# troostite_1_0v.net
KiCad netlist of a schematic drawn in EAGLE
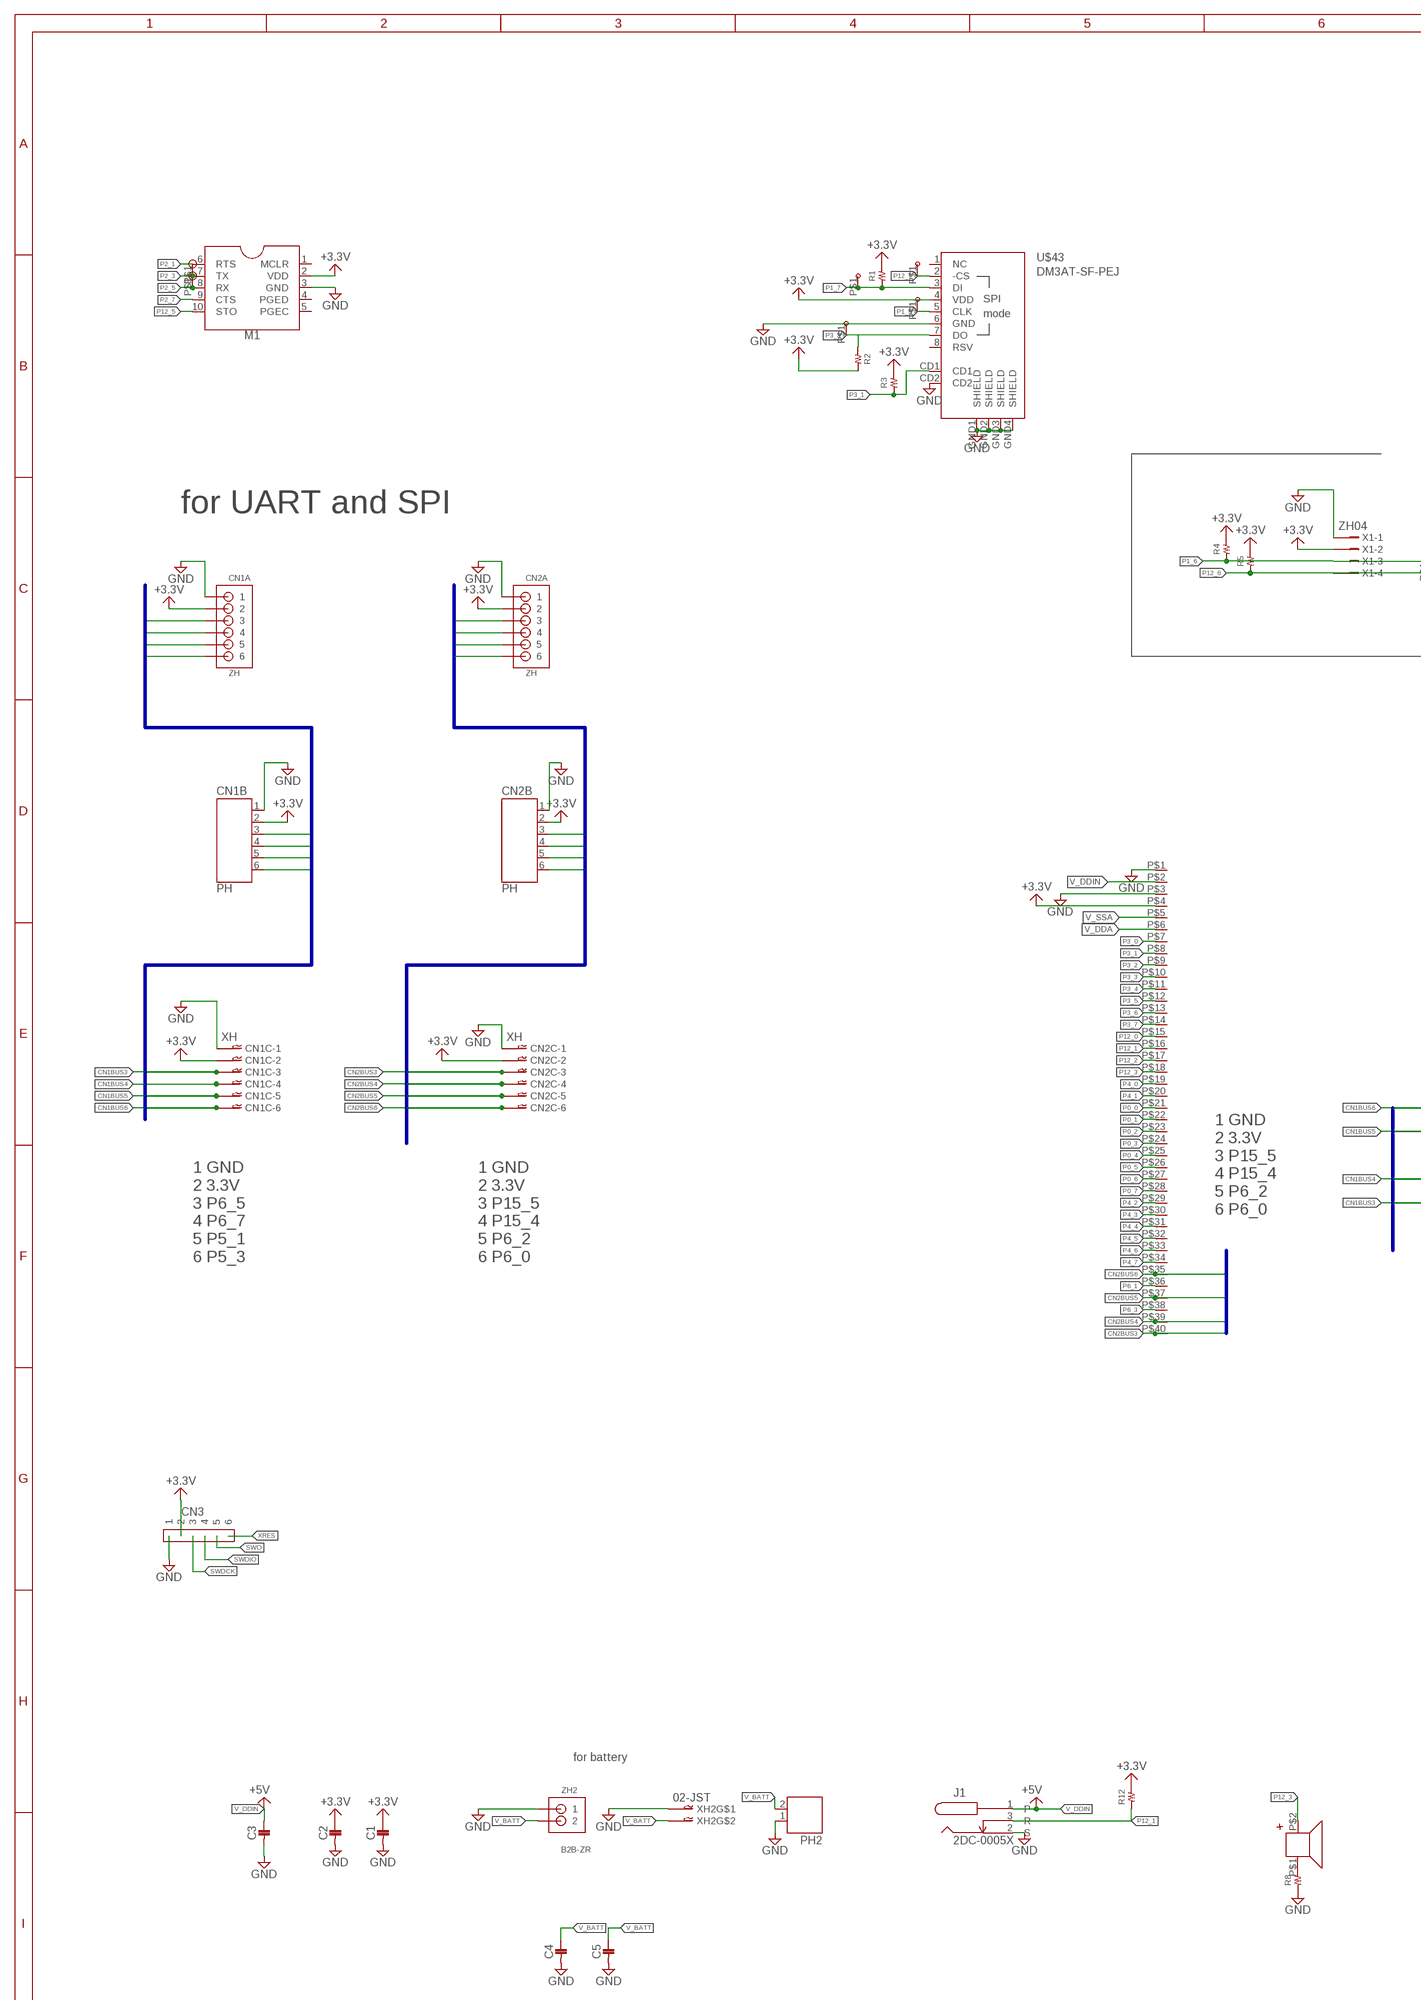
[diagram p0: schematic, sheet 1, part 1 of 2]
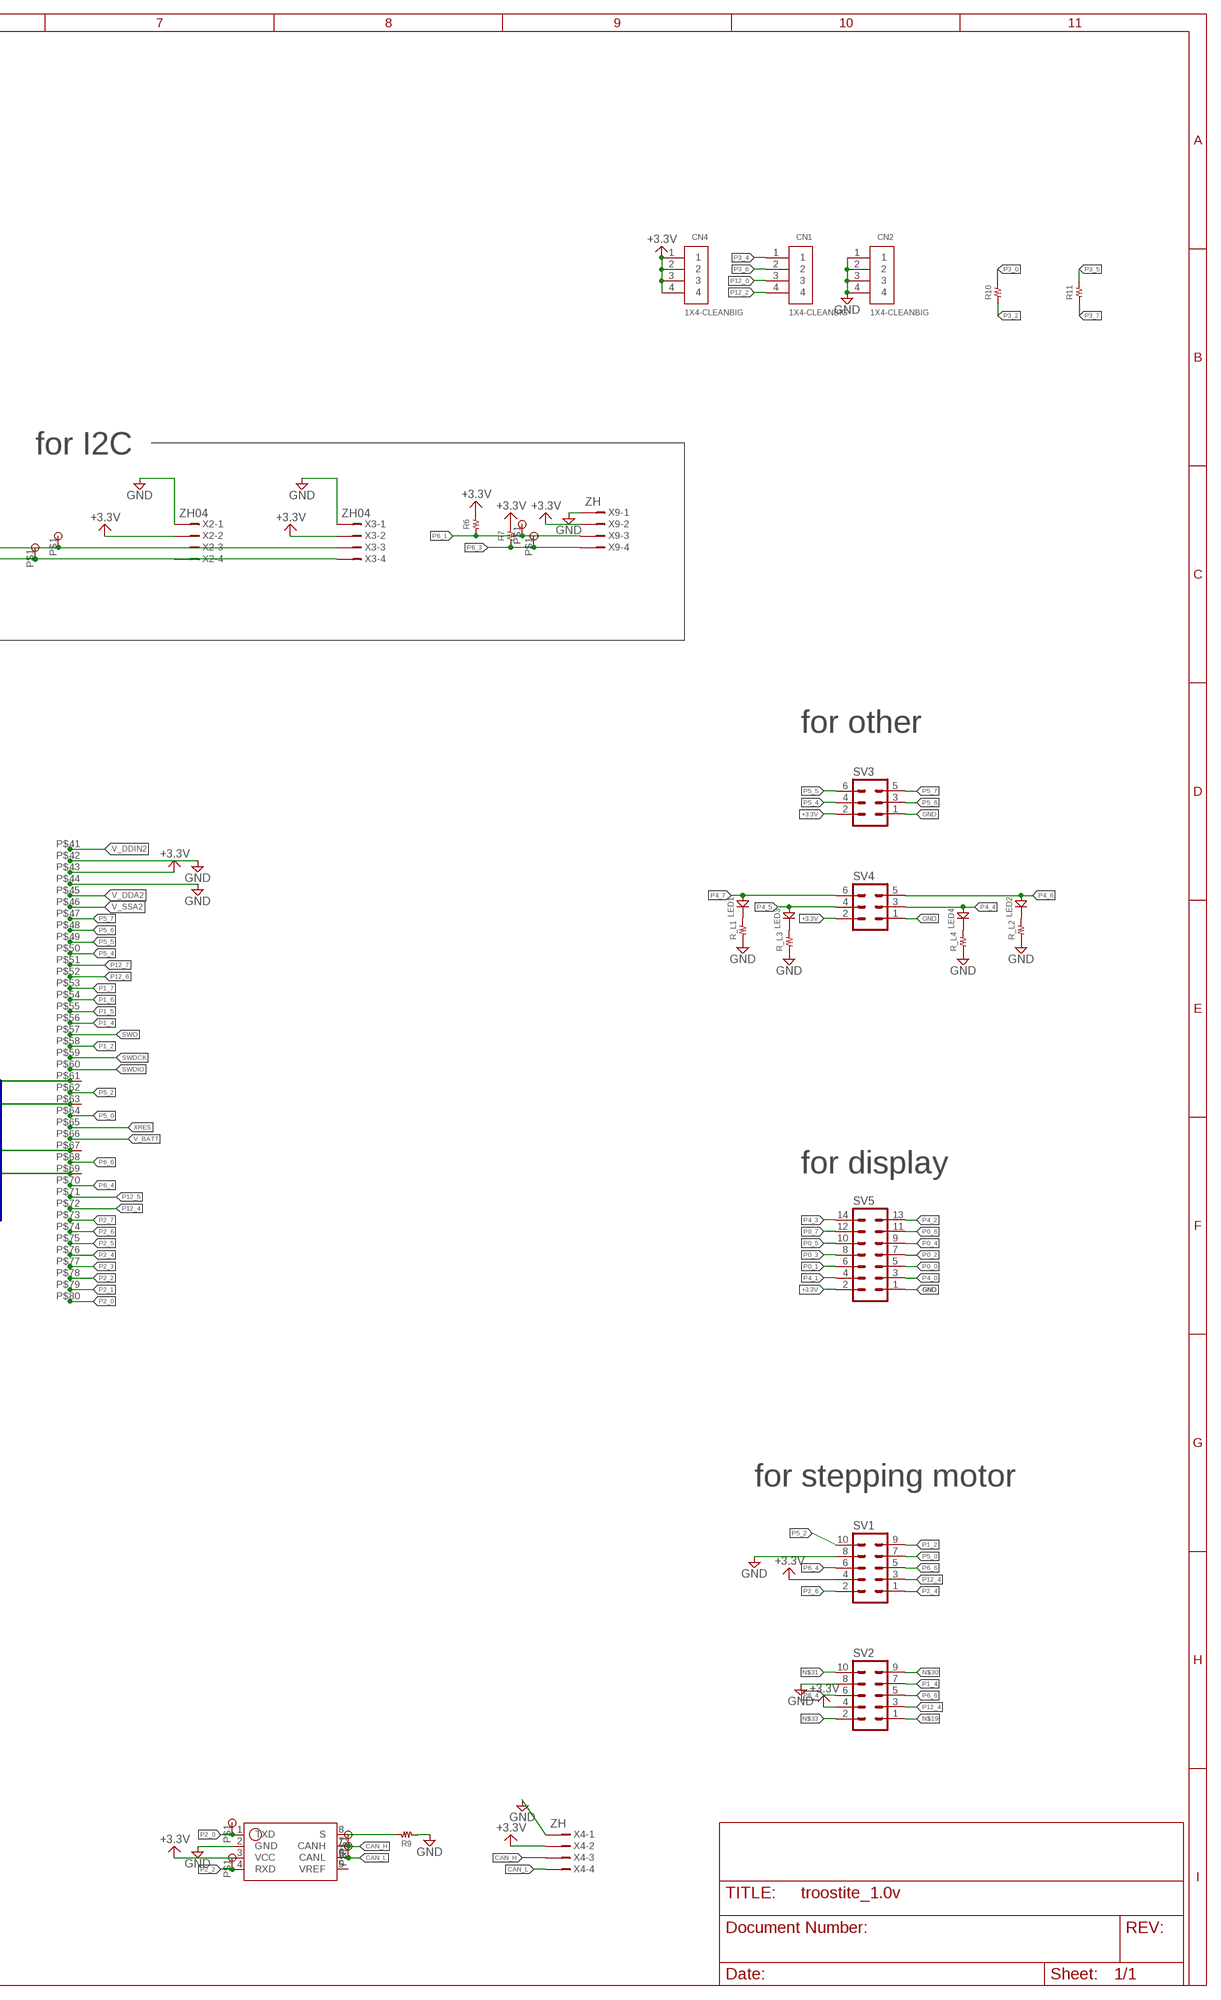
[diagram p1: schematic, sheet 1, part 2 of 2]

(export (version "E")
  (design (tool "Eeschema 10.0.6"))
  (components
    (comp (ref "C1")
      (value "1608")
      (footprint "eagle-import:1608")
      (libsource (lib "eagle-import") (part "1608"))
    )
    (comp (ref "C2")
      (value "1608")
      (footprint "eagle-import:1608")
      (libsource (lib "eagle-import") (part "1608"))
    )
    (comp (ref "C3")
      (value "1608")
      (footprint "eagle-import:1608")
      (libsource (lib "eagle-import") (part "1608"))
    )
    (comp (ref "C4")
      (value "1608")
      (footprint "eagle-import:1608")
      (libsource (lib "eagle-import") (part "1608"))
    )
    (comp (ref "C5")
      (value "3225")
      (footprint "eagle-import:3225")
      (libsource (lib "eagle-import") (part "3225"))
    )
    (comp (ref "CN1")
      (value "1X4-CLEANBIG")
      (footprint "eagle-import:1X04-CLEANBIG")
      (libsource (lib "eagle-import") (part "1X4-CLEANBIG"))
    )
    (comp (ref "CN1A")
      (value "ZH")
      (footprint "eagle-import:B6B-ZR")
      (libsource (lib "eagle-import") (part "B6B-ZR"))
    )
    (comp (ref "CN1B")
      (value "PH")
      (footprint "eagle-import:JST-PH6")
      (libsource (lib "eagle-import") (part "JST-PH6"))
    )
    (comp (ref "CN1C")
      (value "XH")
      (footprint "eagle-import:B6B-XH")
      (libsource (lib "eagle-import") (part "06-JST-B6B-XH-A"))
    )
    (comp (ref "CN2")
      (value "1X4-CLEANBIG")
      (footprint "eagle-import:1X04-CLEANBIG")
      (libsource (lib "eagle-import") (part "1X4-CLEANBIG"))
    )
    (comp (ref "CN2A")
      (value "ZH")
      (footprint "eagle-import:B6B-ZR")
      (libsource (lib "eagle-import") (part "B6B-ZR"))
    )
    (comp (ref "CN2B")
      (value "PH")
      (footprint "eagle-import:JST-PH6")
      (libsource (lib "eagle-import") (part "JST-PH6"))
    )
    (comp (ref "CN2C")
      (value "XH")
      (footprint "eagle-import:B6B-XH")
      (libsource (lib "eagle-import") (part "06-JST-B6B-XH-A"))
    )
    (comp (ref "CN3")
      (value "PIN_HEADER_6")
      (footprint "eagle-import:PIN_HEADER_6")
      (libsource (lib "eagle-import") (part "PIN_HEADER_6"))
    )
    (comp (ref "CN4")
      (value "1X4-CLEANBIG")
      (footprint "eagle-import:1X04-CLEANBIG")
      (libsource (lib "eagle-import") (part "1X4-CLEANBIG"))
    )
    (comp (ref "IC1")
      (value "SN65HVD1050")
      (footprint "eagle-import:SOIC8")
      (libsource (lib "eagle-import") (part "SN65HVD1050"))
    )
    (comp (ref "J1")
      (value "2DC-0005X")
      (footprint "eagle-import:2DC-0005D")
      (libsource (lib "eagle-import") (part "2DC-0005X"))
    )
    (comp (ref "LED1")
      (value "CHIPLED")
      (footprint "eagle-import:1608")
      (libsource (lib "eagle-import") (part "CHIPLED"))
    )
    (comp (ref "LED2")
      (value "CHIPLED")
      (footprint "eagle-import:1608")
      (libsource (lib "eagle-import") (part "CHIPLED"))
    )
    (comp (ref "LED3")
      (value "CHIPLED")
      (footprint "eagle-import:1608")
      (libsource (lib "eagle-import") (part "CHIPLED"))
    )
    (comp (ref "LED4")
      (value "CHIPLED")
      (footprint "eagle-import:1608")
      (libsource (lib "eagle-import") (part "CHIPLED"))
    )
    (comp (ref "M1")
      (value "SBDBT")
      (footprint "eagle-import:DIL10")
      (libsource (lib "eagle-import") (part "SBDBT"))
    )
    (comp (ref "PH2")
      (value "JST-PH2")
      (footprint "eagle-import:JST-PH2")
      (libsource (lib "eagle-import") (part "JST-PH2"))
    )
    (comp (ref "R1")
      (value "RESISTOR__SMD")
      (footprint "eagle-import:1608")
      (libsource (lib "eagle-import") (part "RESISTOR__SMD"))
    )
    (comp (ref "R2")
      (value "RESISTOR__SMD")
      (footprint "eagle-import:1608")
      (libsource (lib "eagle-import") (part "RESISTOR__SMD"))
    )
    (comp (ref "R3")
      (value "RESISTOR__SMD")
      (footprint "eagle-import:1608")
      (libsource (lib "eagle-import") (part "RESISTOR__SMD"))
    )
    (comp (ref "R4")
      (value "RESISTOR__SMD")
      (footprint "eagle-import:1608")
      (libsource (lib "eagle-import") (part "RESISTOR__SMD"))
    )
    (comp (ref "R5")
      (value "RESISTOR__SMD")
      (footprint "eagle-import:1608")
      (libsource (lib "eagle-import") (part "RESISTOR__SMD"))
    )
    (comp (ref "R6")
      (value "RESISTOR__SMD")
      (footprint "eagle-import:1608")
      (libsource (lib "eagle-import") (part "RESISTOR__SMD"))
    )
    (comp (ref "R7")
      (value "RESISTOR__SMD")
      (footprint "eagle-import:1608")
      (libsource (lib "eagle-import") (part "RESISTOR__SMD"))
    )
    (comp (ref "R8")
      (value "RESISTOR__SMD")
      (footprint "eagle-import:1608")
      (libsource (lib "eagle-import") (part "RESISTOR__SMD"))
    )
    (comp (ref "R9")
      (value "RESISTOR__SMD")
      (footprint "eagle-import:1608")
      (libsource (lib "eagle-import") (part "RESISTOR__SMD"))
    )
    (comp (ref "R10")
      (value "RESISTOR__SMD")
      (footprint "eagle-import:1608")
      (libsource (lib "eagle-import") (part "RESISTOR__SMD"))
    )
    (comp (ref "R11")
      (value "RESISTOR__SMD")
      (footprint "eagle-import:1608")
      (libsource (lib "eagle-import") (part "RESISTOR__SMD"))
    )
    (comp (ref "R12")
      (value "RESISTOR__SMD")
      (footprint "eagle-import:1608")
      (libsource (lib "eagle-import") (part "RESISTOR__SMD"))
    )
    (comp (ref "R_L1")
      (value "RESISTOR__SMD")
      (footprint "eagle-import:1608")
      (libsource (lib "eagle-import") (part "RESISTOR__SMD"))
    )
    (comp (ref "R_L2")
      (value "RESISTOR__SMD")
      (footprint "eagle-import:1608")
      (libsource (lib "eagle-import") (part "RESISTOR__SMD"))
    )
    (comp (ref "R_L3")
      (value "RESISTOR__SMD")
      (footprint "eagle-import:1608")
      (libsource (lib "eagle-import") (part "RESISTOR__SMD"))
    )
    (comp (ref "R_L4")
      (value "RESISTOR__SMD")
      (footprint "eagle-import:1608")
      (libsource (lib "eagle-import") (part "RESISTOR__SMD"))
    )
    (comp (ref "SV1")
      (value "ML10")
      (footprint "eagle-import:ML10")
      (libsource (lib "eagle-import") (part "ML10"))
    )
    (comp (ref "SV2")
      (value "ML10")
      (footprint "eagle-import:ML10")
      (libsource (lib "eagle-import") (part "ML10"))
    )
    (comp (ref "SV3")
      (value "ML6")
      (footprint "eagle-import:ML6")
      (libsource (lib "eagle-import") (part "ML6"))
    )
    (comp (ref "SV4")
      (value "ML6")
      (footprint "eagle-import:ML6")
      (libsource (lib "eagle-import") (part "ML6"))
    )
    (comp (ref "SV5")
      (value "ML14")
      (footprint "eagle-import:ML14")
      (libsource (lib "eagle-import") (part "ML14"))
    )
    (comp (ref "U$2")
      (value "PSOC_5LP")
      (footprint "eagle-import:PSOC_5LP")
      (libsource (lib "eagle-import") (part "PSOC_5LP"))
    )
    (comp (ref "U$41")
      (value "PKLCS1212E4001")
      (footprint "eagle-import:PKLCS1212E4001")
      (libsource (lib "eagle-import") (part "PKLCS1212E4001"))
    )
    (comp (ref "U$43")
      (value "DM3AT-SF-PEJ")
      (footprint "eagle-import:DM3AT-SF-PEJ")
      (libsource (lib "eagle-import") (part "DM3AT-SF-PEJ"))
    )
    (comp (ref "U$72")
      (value "CHECK_0.8MM")
      (footprint "eagle-import:CHECK_0.8MM")
      (libsource (lib "eagle-import") (part "CHECK_0.8MM"))
    )
    (comp (ref "U$73")
      (value "CHECK_0.8MM")
      (footprint "eagle-import:CHECK_0.8MM")
      (libsource (lib "eagle-import") (part "CHECK_0.8MM"))
    )
    (comp (ref "U$74")
      (value "CHECK_0.8MM")
      (footprint "eagle-import:CHECK_0.8MM")
      (libsource (lib "eagle-import") (part "CHECK_0.8MM"))
    )
    (comp (ref "U$75")
      (value "CHECK_0.8MM")
      (footprint "eagle-import:CHECK_0.8MM")
      (libsource (lib "eagle-import") (part "CHECK_0.8MM"))
    )
    (comp (ref "U$76")
      (value "CHECK_0.8MM")
      (footprint "eagle-import:CHECK_0.8MM")
      (libsource (lib "eagle-import") (part "CHECK_0.8MM"))
    )
    (comp (ref "U$77")
      (value "CHECK_0.8MM")
      (footprint "eagle-import:CHECK_0.8MM")
      (libsource (lib "eagle-import") (part "CHECK_0.8MM"))
    )
    (comp (ref "U$78")
      (value "CHECK_0.8MM")
      (footprint "eagle-import:CHECK_0.8MM")
      (libsource (lib "eagle-import") (part "CHECK_0.8MM"))
    )
    (comp (ref "U$79")
      (value "CHECK_0.8MM")
      (footprint "eagle-import:CHECK_0.8MM")
      (libsource (lib "eagle-import") (part "CHECK_0.8MM"))
    )
    (comp (ref "U$82")
      (value "CHECK_0.8MM")
      (footprint "eagle-import:CHECK_0.8MM")
      (libsource (lib "eagle-import") (part "CHECK_0.8MM"))
    )
    (comp (ref "U$83")
      (value "CHECK_0.8MM")
      (footprint "eagle-import:CHECK_0.8MM")
      (libsource (lib "eagle-import") (part "CHECK_0.8MM"))
    )
    (comp (ref "U$85")
      (value "CHECK_21.3")
      (footprint "eagle-import:CHECK_2_1.3")
      (libsource (lib "eagle-import") (part "CHECK_21.3"))
    )
    (comp (ref "U$86")
      (value "CHECK_21.3")
      (footprint "eagle-import:CHECK_2_1.3")
      (libsource (lib "eagle-import") (part "CHECK_21.3"))
    )
    (comp (ref "U$87")
      (value "CHECK_21.3")
      (footprint "eagle-import:CHECK_2_1.3")
      (libsource (lib "eagle-import") (part "CHECK_21.3"))
    )
    (comp (ref "U$88")
      (value "CHECK_21.3")
      (footprint "eagle-import:CHECK_2_1.3")
      (libsource (lib "eagle-import") (part "CHECK_21.3"))
    )
    (comp (ref "X1")
      (value "ZH04")
      (footprint "eagle-import:B4B-ZR")
      (fields (field (name "MF") "FARNELL") (field (name "MPN") "B4B-ZR(LF)(SN)"))
      (libsource (lib "eagle-import") (part "?4B-ZRB"))
    )
    (comp (ref "X2")
      (value "ZH04")
      (footprint "eagle-import:B4B-ZR")
      (fields (field (name "MF") "FARNELL") (field (name "MPN") "B4B-ZR(LF)(SN)"))
      (libsource (lib "eagle-import") (part "?4B-ZRB"))
    )
    (comp (ref "X3")
      (value "ZH04")
      (footprint "eagle-import:B4B-ZR")
      (fields (field (name "MF") "FARNELL") (field (name "MPN") "B4B-ZR(LF)(SN)"))
      (libsource (lib "eagle-import") (part "?4B-ZRB"))
    )
    (comp (ref "X4")
      (value "ZH")
      (footprint "eagle-import:B4B-ZR")
      (fields (field (name "MF") "FARNELL") (field (name "MPN") "B4B-ZR(LF)(SN)"))
      (libsource (lib "eagle-import") (part "?4B-ZRB"))
    )
    (comp (ref "X9")
      (value "ZH")
      (footprint "eagle-import:B4B-ZR")
      (fields (field (name "MF") "FARNELL") (field (name "MPN") "B4B-ZR(LF)(SN)"))
      (libsource (lib "eagle-import") (part "?4B-ZRB"))
    )
    (comp (ref "XH2")
      (value "02-JST")
      (footprint "eagle-import:B2B-XH")
      (libsource (lib "eagle-import") (part "02-JST"))
    )
    (comp (ref "ZH2")
      (value "B2B-ZR")
      (footprint "eagle-import:B2B-ZR")
      (libsource (lib "eagle-import") (part "B2B-ZR"))
    )
  )
  (nets
    (net (code "1") (name "+3.3V") (class "Default")
      (node (ref "C1") (pin "P$1") (pinfunction "1_P$1") (pintype "passive"))
      (node (ref "C2") (pin "P$1") (pinfunction "1_P$1") (pintype "passive"))
      (node (ref "CN1A") (pin "2") (pinfunction "2_2") (pintype "bidirectional"))
      (node (ref "CN1B") (pin "2") (pinfunction "2_2") (pintype "passive"))
      (node (ref "CN1C") (pin "P$2") (pinfunction "1_P$2") (pintype "passive"))
      (node (ref "CN2A") (pin "2") (pinfunction "2_2") (pintype "bidirectional"))
      (node (ref "CN2B") (pin "2") (pinfunction "2_2") (pintype "passive"))
      (node (ref "CN2C") (pin "P$2") (pinfunction "1_P$2") (pintype "passive"))
      (node (ref "CN3") (pin "2") (pinfunction "2_2") (pintype "bidirectional"))
      (node (ref "CN4") (pin "1") (pinfunction "1_1") (pintype "bidirectional"))
      (node (ref "CN4") (pin "2") (pinfunction "2_2") (pintype "bidirectional"))
      (node (ref "CN4") (pin "3") (pinfunction "3_3") (pintype "bidirectional"))
      (node (ref "CN4") (pin "4") (pinfunction "4_4") (pintype "bidirectional"))
      (node (ref "IC1") (pin "3") (pinfunction "VCC_3") (pintype "bidirectional"))
      (node (ref "M1") (pin "2") (pinfunction "VDD_2") (pintype "passive"))
      (node (ref "R1") (pin "2") (pinfunction "P$2_2") (pintype "passive"))
      (node (ref "R12") (pin "2") (pinfunction "P$2_2") (pintype "passive"))
      (node (ref "R2") (pin "2") (pinfunction "P$2_2") (pintype "passive"))
      (node (ref "R3") (pin "2") (pinfunction "P$2_2") (pintype "passive"))
      (node (ref "R4") (pin "2") (pinfunction "P$2_2") (pintype "passive"))
      (node (ref "R5") (pin "2") (pinfunction "P$2_2") (pintype "passive"))
      (node (ref "R6") (pin "2") (pinfunction "P$2_2") (pintype "passive"))
      (node (ref "R7") (pin "2") (pinfunction "P$2_2") (pintype "passive"))
      (node (ref "SV1") (pin "4") (pinfunction "4_4") (pintype "passive"))
      (node (ref "SV2") (pin "4") (pinfunction "4_4") (pintype "passive"))
      (node (ref "SV3") (pin "2") (pinfunction "2_2") (pintype "passive"))
      (node (ref "SV4") (pin "2") (pinfunction "2_2") (pintype "passive"))
      (node (ref "SV5") (pin "2") (pinfunction "2_2") (pintype "passive"))
      (node (ref "U$2") (pin "P$4") (pinfunction "P$4_P$4") (pintype "bidirectional"))
      (node (ref "U$2") (pin "P$43") (pinfunction "P$43_P$43") (pintype "bidirectional"))
      (node (ref "U$43") (pin "4") (pinfunction "VDD_4") (pintype "bidirectional"))
      (node (ref "X1") (pin "2") (pinfunction "1_2") (pintype "passive"))
      (node (ref "X2") (pin "2") (pinfunction "1_2") (pintype "passive"))
      (node (ref "X3") (pin "2") (pinfunction "1_2") (pintype "passive"))
      (node (ref "X4") (pin "2") (pinfunction "1_2") (pintype "passive"))
      (node (ref "X9") (pin "2") (pinfunction "1_2") (pintype "passive"))
    )
    (net (code "4") (name "CAN_H") (class "Default")
      (node (ref "IC1") (pin "7") (pinfunction "CANH_7") (pintype "bidirectional"))
      (node (ref "U$72") (pin "P$1") (pinfunction "P$1_P$1") (pintype "bidirectional"))
      (node (ref "X4") (pin "3") (pinfunction "1_3") (pintype "passive"))
    )
    (net (code "5") (name "CAN_L") (class "Default")
      (node (ref "IC1") (pin "6") (pinfunction "CANL_6") (pintype "bidirectional"))
      (node (ref "U$73") (pin "P$1") (pinfunction "P$1_P$1") (pintype "bidirectional"))
      (node (ref "X4") (pin "4") (pinfunction "1_4") (pintype "passive"))
    )
    (net (code "6") (name "CN1BUS3") (class "Default")
      (node (ref "CN1A") (pin "3") (pinfunction "3_3") (pintype "bidirectional"))
      (node (ref "CN1B") (pin "3") (pinfunction "3_3") (pintype "passive"))
      (node (ref "CN1C") (pin "P$3") (pinfunction "1_P$3") (pintype "passive"))
      (node (ref "U$2") (pin "P$69") (pinfunction "P$69_P$69") (pintype "bidirectional"))
    )
    (net (code "7") (name "CN1BUS4") (class "Default")
      (node (ref "CN1A") (pin "4") (pinfunction "4_4") (pintype "bidirectional"))
      (node (ref "CN1B") (pin "4") (pinfunction "4_4") (pintype "passive"))
      (node (ref "CN1C") (pin "P$4") (pinfunction "1_P$4") (pintype "passive"))
      (node (ref "U$2") (pin "P$67") (pinfunction "P$67_P$67") (pintype "bidirectional"))
    )
    (net (code "8") (name "CN1BUS5") (class "Default")
      (node (ref "CN1A") (pin "5") (pinfunction "5_5") (pintype "bidirectional"))
      (node (ref "CN1B") (pin "5") (pinfunction "5_5") (pintype "passive"))
      (node (ref "CN1C") (pin "P$5") (pinfunction "1_P$5") (pintype "passive"))
      (node (ref "U$2") (pin "P$63") (pinfunction "P$63_P$63") (pintype "bidirectional"))
    )
    (net (code "9") (name "CN1BUS6") (class "Default")
      (node (ref "CN1A") (pin "6") (pinfunction "6_6") (pintype "bidirectional"))
      (node (ref "CN1B") (pin "6") (pinfunction "6_6") (pintype "passive"))
      (node (ref "CN1C") (pin "P$6") (pinfunction "1_P$6") (pintype "passive"))
      (node (ref "U$2") (pin "P$61") (pinfunction "P$61_P$61") (pintype "bidirectional"))
    )
    (net (code "10") (name "CN2BUS3") (class "Default")
      (node (ref "CN2A") (pin "3") (pinfunction "3_3") (pintype "bidirectional"))
      (node (ref "CN2B") (pin "3") (pinfunction "3_3") (pintype "passive"))
      (node (ref "CN2C") (pin "P$3") (pinfunction "1_P$3") (pintype "passive"))
      (node (ref "U$2") (pin "P$40") (pinfunction "P$40_P$40") (pintype "bidirectional"))
    )
    (net (code "11") (name "CN2BUS4") (class "Default")
      (node (ref "CN2A") (pin "4") (pinfunction "4_4") (pintype "bidirectional"))
      (node (ref "CN2B") (pin "4") (pinfunction "4_4") (pintype "passive"))
      (node (ref "CN2C") (pin "P$4") (pinfunction "1_P$4") (pintype "passive"))
      (node (ref "U$2") (pin "P$39") (pinfunction "P$39_P$39") (pintype "bidirectional"))
    )
    (net (code "12") (name "CN2BUS5") (class "Default")
      (node (ref "CN2A") (pin "5") (pinfunction "5_5") (pintype "bidirectional"))
      (node (ref "CN2B") (pin "5") (pinfunction "5_5") (pintype "passive"))
      (node (ref "CN2C") (pin "P$5") (pinfunction "1_P$5") (pintype "passive"))
      (node (ref "U$2") (pin "P$37") (pinfunction "P$37_P$37") (pintype "bidirectional"))
    )
    (net (code "13") (name "CN2BUS6") (class "Default")
      (node (ref "CN2A") (pin "6") (pinfunction "6_6") (pintype "bidirectional"))
      (node (ref "CN2B") (pin "6") (pinfunction "6_6") (pintype "passive"))
      (node (ref "CN2C") (pin "P$6") (pinfunction "1_P$6") (pintype "passive"))
      (node (ref "U$2") (pin "P$35") (pinfunction "P$35_P$35") (pintype "bidirectional"))
    )
    (net (code "14") (name "GND") (class "Default")
      (node (ref "C1") (pin "P$2") (pinfunction "2_P$2") (pintype "passive"))
      (node (ref "C2") (pin "P$2") (pinfunction "2_P$2") (pintype "passive"))
      (node (ref "C3") (pin "P$2") (pinfunction "2_P$2") (pintype "passive"))
      (node (ref "C4") (pin "P$2") (pinfunction "2_P$2") (pintype "passive"))
      (node (ref "C5") (pin "P$2") (pinfunction "2_P$2") (pintype "passive"))
      (node (ref "CN1A") (pin "1") (pinfunction "1_1") (pintype "bidirectional"))
      (node (ref "CN1B") (pin "1") (pinfunction "1_1") (pintype "passive"))
      (node (ref "CN1C") (pin "P$1") (pinfunction "1_P$1") (pintype "passive"))
      (node (ref "CN2") (pin "1") (pinfunction "1_1") (pintype "bidirectional"))
      (node (ref "CN2") (pin "2") (pinfunction "2_2") (pintype "bidirectional"))
      (node (ref "CN2") (pin "3") (pinfunction "3_3") (pintype "bidirectional"))
      (node (ref "CN2") (pin "4") (pinfunction "4_4") (pintype "bidirectional"))
      (node (ref "CN2A") (pin "1") (pinfunction "1_1") (pintype "bidirectional"))
      (node (ref "CN2B") (pin "1") (pinfunction "1_1") (pintype "passive"))
      (node (ref "CN2C") (pin "P$1") (pinfunction "1_P$1") (pintype "passive"))
      (node (ref "CN3") (pin "1") (pinfunction "1_1") (pintype "bidirectional"))
      (node (ref "IC1") (pin "2") (pinfunction "GND_2") (pintype "bidirectional"))
      (node (ref "J1") (pin "2") (pinfunction "S_2") (pintype "power_in"))
      (node (ref "M1") (pin "3") (pinfunction "GND_3") (pintype "passive"))
      (node (ref "PH2") (pin "1") (pinfunction "1_1") (pintype "passive"))
      (node (ref "R8") (pin "1") (pinfunction "P$1_1") (pintype "passive"))
      (node (ref "R9") (pin "1") (pinfunction "P$1_1") (pintype "passive"))
      (node (ref "R_L1") (pin "1") (pinfunction "P$1_1") (pintype "passive"))
      (node (ref "R_L2") (pin "1") (pinfunction "P$1_1") (pintype "passive"))
      (node (ref "R_L3") (pin "1") (pinfunction "P$1_1") (pintype "passive"))
      (node (ref "R_L4") (pin "1") (pinfunction "P$1_1") (pintype "passive"))
      (node (ref "SV1") (pin "8") (pinfunction "8_8") (pintype "passive"))
      (node (ref "SV2") (pin "8") (pinfunction "8_8") (pintype "passive"))
      (node (ref "SV3") (pin "1") (pinfunction "1_1") (pintype "passive"))
      (node (ref "SV4") (pin "1") (pinfunction "1_1") (pintype "passive"))
      (node (ref "SV5") (pin "1") (pinfunction "1_1") (pintype "passive"))
      (node (ref "U$2") (pin "P$1") (pinfunction "P$1_P$1") (pintype "bidirectional"))
      (node (ref "U$2") (pin "P$3") (pinfunction "P$3_P$3") (pintype "bidirectional"))
      (node (ref "U$2") (pin "P$42") (pinfunction "P$42_P$42") (pintype "bidirectional"))
      (node (ref "U$2") (pin "P$44") (pinfunction "P$44_P$44") (pintype "bidirectional"))
      (node (ref "U$43") (pin "6") (pinfunction "GND_6") (pintype "bidirectional"))
      (node (ref "U$43") (pin "CD2") (pinfunction "CD2_CD2") (pintype "bidirectional"))
      (node (ref "U$43") (pin "GND1") (pinfunction "SHIELD_GND1") (pintype "bidirectional"))
      (node (ref "U$43") (pin "GND2") (pinfunction "SHIELD_GND2") (pintype "bidirectional"))
      (node (ref "U$43") (pin "GND3") (pinfunction "SHIELD_GND3") (pintype "bidirectional"))
      (node (ref "U$43") (pin "GND4") (pinfunction "SHIELD_GND4") (pintype "bidirectional"))
      (node (ref "X1") (pin "1") (pinfunction "1_1") (pintype "passive"))
      (node (ref "X2") (pin "1") (pinfunction "1_1") (pintype "passive"))
      (node (ref "X3") (pin "1") (pinfunction "1_1") (pintype "passive"))
      (node (ref "X4") (pin "1") (pinfunction "1_1") (pintype "passive"))
      (node (ref "X9") (pin "1") (pinfunction "1_1") (pintype "passive"))
      (node (ref "XH2") (pin "P$1") (pinfunction "1_P$1") (pintype "passive"))
      (node (ref "ZH2") (pin "1") (pinfunction "1_1") (pintype "bidirectional"))
    )
    (net (code "15") (name "N$19") (class "Default")
      (node (ref "SV2") (pin "1") (pinfunction "1_1") (pintype "passive"))
    )
    (net (code "16") (name "N$30") (class "Default")
      (node (ref "SV2") (pin "9") (pinfunction "9_9") (pintype "passive"))
    )
    (net (code "17") (name "N$31") (class "Default")
      (node (ref "SV2") (pin "10") (pinfunction "10_10") (pintype "passive"))
    )
    (net (code "18") (name "N$33") (class "Default")
      (node (ref "SV2") (pin "2") (pinfunction "2_2") (pintype "passive"))
    )
    (net (code "19") (name "Net-(IC1-S)") (class "Default")
      (node (ref "IC1") (pin "8") (pinfunction "S_8") (pintype "bidirectional"))
      (node (ref "R9") (pin "2") (pinfunction "P$2_2") (pintype "passive"))
    )
    (net (code "20") (name "Net-(LED1-K)") (class "Default")
      (node (ref "LED1") (pin "2") (pinfunction "K_2") (pintype "bidirectional"))
      (node (ref "R_L1") (pin "2") (pinfunction "P$2_2") (pintype "passive"))
    )
    (net (code "21") (name "Net-(LED2-K)") (class "Default")
      (node (ref "LED2") (pin "2") (pinfunction "K_2") (pintype "bidirectional"))
      (node (ref "R_L2") (pin "2") (pinfunction "P$2_2") (pintype "passive"))
    )
    (net (code "22") (name "Net-(LED3-K)") (class "Default")
      (node (ref "LED3") (pin "2") (pinfunction "K_2") (pintype "bidirectional"))
      (node (ref "R_L3") (pin "2") (pinfunction "P$2_2") (pintype "passive"))
    )
    (net (code "23") (name "Net-(LED4-K)") (class "Default")
      (node (ref "LED4") (pin "2") (pinfunction "K_2") (pintype "bidirectional"))
      (node (ref "R_L4") (pin "2") (pinfunction "P$2_2") (pintype "passive"))
    )
    (net (code "24") (name "Net-(R8-P$2)") (class "Default")
      (node (ref "R8") (pin "2") (pinfunction "P$2_2") (pintype "passive"))
      (node (ref "U$41") (pin "P$1") (pinfunction "MINUS_P$1") (pintype "bidirectional"))
    )
    (net (code "25") (name "P0_0") (class "Default")
      (node (ref "SV5") (pin "5") (pinfunction "5_5") (pintype "passive"))
      (node (ref "U$2") (pin "P$21") (pinfunction "P$21_P$21") (pintype "bidirectional"))
    )
    (net (code "26") (name "P0_1") (class "Default")
      (node (ref "SV5") (pin "6") (pinfunction "6_6") (pintype "passive"))
      (node (ref "U$2") (pin "P$22") (pinfunction "P$22_P$22") (pintype "bidirectional"))
    )
    (net (code "27") (name "P0_2") (class "Default")
      (node (ref "SV5") (pin "7") (pinfunction "7_7") (pintype "passive"))
      (node (ref "U$2") (pin "P$23") (pinfunction "P$23_P$23") (pintype "bidirectional"))
    )
    (net (code "28") (name "P0_3") (class "Default")
      (node (ref "SV5") (pin "8") (pinfunction "8_8") (pintype "passive"))
      (node (ref "U$2") (pin "P$24") (pinfunction "P$24_P$24") (pintype "bidirectional"))
    )
    (net (code "29") (name "P0_4") (class "Default")
      (node (ref "SV5") (pin "9") (pinfunction "9_9") (pintype "passive"))
      (node (ref "U$2") (pin "P$25") (pinfunction "P$25_P$25") (pintype "bidirectional"))
    )
    (net (code "30") (name "P0_5") (class "Default")
      (node (ref "SV5") (pin "10") (pinfunction "10_10") (pintype "passive"))
      (node (ref "U$2") (pin "P$26") (pinfunction "P$26_P$26") (pintype "bidirectional"))
    )
    (net (code "31") (name "P0_6") (class "Default")
      (node (ref "SV5") (pin "11") (pinfunction "11_11") (pintype "passive"))
      (node (ref "U$2") (pin "P$27") (pinfunction "P$27_P$27") (pintype "bidirectional"))
    )
    (net (code "32") (name "P0_7") (class "Default")
      (node (ref "SV5") (pin "12") (pinfunction "12_12") (pintype "passive"))
      (node (ref "U$2") (pin "P$28") (pinfunction "P$28_P$28") (pintype "bidirectional"))
    )
    (net (code "33") (name "P1_2") (class "Default")
      (node (ref "SV1") (pin "9") (pinfunction "9_9") (pintype "passive"))
      (node (ref "U$2") (pin "P$58") (pinfunction "P$58_P$58") (pintype "bidirectional"))
    )
    (net (code "34") (name "P1_4") (class "Default")
      (node (ref "SV2") (pin "7") (pinfunction "7_7") (pintype "passive"))
      (node (ref "U$2") (pin "P$56") (pinfunction "P$56_P$56") (pintype "bidirectional"))
    )
    (net (code "35") (name "P1_5") (class "Default")
      (node (ref "U$2") (pin "P$55") (pinfunction "P$55_P$55") (pintype "bidirectional"))
      (node (ref "U$43") (pin "5") (pinfunction "CLK_5") (pintype "bidirectional"))
      (node (ref "U$87") (pin "P$1") (pinfunction "P$1_P$1") (pintype "bidirectional"))
    )
    (net (code "36") (name "P1_6") (class "Default")
      (node (ref "R4") (pin "1") (pinfunction "P$1_1") (pintype "passive"))
      (node (ref "U$2") (pin "P$54") (pinfunction "P$54_P$54") (pintype "bidirectional"))
      (node (ref "U$76") (pin "P$1") (pinfunction "P$1_P$1") (pintype "bidirectional"))
      (node (ref "X1") (pin "3") (pinfunction "1_3") (pintype "passive"))
      (node (ref "X2") (pin "3") (pinfunction "1_3") (pintype "passive"))
      (node (ref "X3") (pin "3") (pinfunction "1_3") (pintype "passive"))
    )
    (net (code "37") (name "P1_7") (class "Default")
      (node (ref "R1") (pin "1") (pinfunction "P$1_1") (pintype "passive"))
      (node (ref "U$2") (pin "P$53") (pinfunction "P$53_P$53") (pintype "bidirectional"))
      (node (ref "U$43") (pin "3") (pinfunction "DI_3") (pintype "bidirectional"))
      (node (ref "U$85") (pin "P$1") (pinfunction "P$1_P$1") (pintype "bidirectional"))
    )
    (net (code "38") (name "P2_0") (class "Default")
      (node (ref "IC1") (pin "1") (pinfunction "TXD_1") (pintype "bidirectional"))
      (node (ref "U$2") (pin "P$80") (pinfunction "P$80_P$80") (pintype "bidirectional"))
      (node (ref "U$74") (pin "P$1") (pinfunction "P$1_P$1") (pintype "bidirectional"))
    )
    (net (code "39") (name "P2_1") (class "Default")
      (node (ref "M1") (pin "6") (pinfunction "RTS_6") (pintype "passive"))
      (node (ref "U$2") (pin "P$79") (pinfunction "P$79_P$79") (pintype "bidirectional"))
    )
    (net (code "40") (name "P2_2") (class "Default")
      (node (ref "IC1") (pin "4") (pinfunction "RXD_4") (pintype "bidirectional"))
      (node (ref "U$2") (pin "P$78") (pinfunction "P$78_P$78") (pintype "bidirectional"))
      (node (ref "U$75") (pin "P$1") (pinfunction "P$1_P$1") (pintype "bidirectional"))
    )
    (net (code "41") (name "P2_3") (class "Default")
      (node (ref "M1") (pin "7") (pinfunction "TX_7") (pintype "passive"))
      (node (ref "U$2") (pin "P$77") (pinfunction "P$77_P$77") (pintype "bidirectional"))
      (node (ref "U$82") (pin "P$1") (pinfunction "P$1_P$1") (pintype "bidirectional"))
    )
    (net (code "42") (name "P2_4") (class "Default")
      (node (ref "SV1") (pin "1") (pinfunction "1_1") (pintype "passive"))
      (node (ref "U$2") (pin "P$76") (pinfunction "P$76_P$76") (pintype "bidirectional"))
    )
    (net (code "43") (name "P2_5") (class "Default")
      (node (ref "M1") (pin "8") (pinfunction "RX_8") (pintype "passive"))
      (node (ref "U$2") (pin "P$75") (pinfunction "P$75_P$75") (pintype "bidirectional"))
      (node (ref "U$83") (pin "P$1") (pinfunction "P$1_P$1") (pintype "bidirectional"))
    )
    (net (code "44") (name "P2_6") (class "Default")
      (node (ref "SV1") (pin "2") (pinfunction "2_2") (pintype "passive"))
      (node (ref "U$2") (pin "P$74") (pinfunction "P$74_P$74") (pintype "bidirectional"))
    )
    (net (code "45") (name "P2_7") (class "Default")
      (node (ref "M1") (pin "9") (pinfunction "CTS_9") (pintype "passive"))
      (node (ref "U$2") (pin "P$73") (pinfunction "P$73_P$73") (pintype "bidirectional"))
    )
    (net (code "46") (name "P3_0") (class "Default")
      (node (ref "R10") (pin "2") (pinfunction "P$2_2") (pintype "passive"))
      (node (ref "U$2") (pin "P$7") (pinfunction "P$7_P$7") (pintype "bidirectional"))
    )
    (net (code "47") (name "P3_1") (class "Default")
      (node (ref "R3") (pin "1") (pinfunction "P$1_1") (pintype "passive"))
      (node (ref "U$2") (pin "P$8") (pinfunction "P$8_P$8") (pintype "bidirectional"))
      (node (ref "U$43") (pin "CD1") (pinfunction "CD1_CD1") (pintype "bidirectional"))
    )
    (net (code "48") (name "P3_2") (class "Default")
      (node (ref "R10") (pin "1") (pinfunction "P$1_1") (pintype "passive"))
      (node (ref "U$2") (pin "P$9") (pinfunction "P$9_P$9") (pintype "bidirectional"))
    )
    (net (code "49") (name "P3_3") (class "Default")
      (node (ref "R2") (pin "1") (pinfunction "P$1_1") (pintype "passive"))
      (node (ref "U$2") (pin "P$10") (pinfunction "P$10_P$10") (pintype "bidirectional"))
      (node (ref "U$43") (pin "7") (pinfunction "DO_7") (pintype "bidirectional"))
      (node (ref "U$88") (pin "P$1") (pinfunction "P$1_P$1") (pintype "bidirectional"))
    )
    (net (code "50") (name "P3_4") (class "Default")
      (node (ref "CN1") (pin "1") (pinfunction "1_1") (pintype "bidirectional"))
      (node (ref "U$2") (pin "P$11") (pinfunction "P$11_P$11") (pintype "bidirectional"))
    )
    (net (code "51") (name "P3_5") (class "Default")
      (node (ref "R11") (pin "2") (pinfunction "P$2_2") (pintype "passive"))
      (node (ref "U$2") (pin "P$12") (pinfunction "P$12_P$12") (pintype "bidirectional"))
    )
    (net (code "52") (name "P3_6") (class "Default")
      (node (ref "CN1") (pin "2") (pinfunction "2_2") (pintype "bidirectional"))
      (node (ref "U$2") (pin "P$13") (pinfunction "P$13_P$13") (pintype "bidirectional"))
    )
    (net (code "53") (name "P3_7") (class "Default")
      (node (ref "R11") (pin "1") (pinfunction "P$1_1") (pintype "passive"))
      (node (ref "U$2") (pin "P$14") (pinfunction "P$14_P$14") (pintype "bidirectional"))
    )
    (net (code "54") (name "P4_0") (class "Default")
      (node (ref "SV5") (pin "3") (pinfunction "3_3") (pintype "passive"))
      (node (ref "U$2") (pin "P$19") (pinfunction "P$19_P$19") (pintype "bidirectional"))
    )
    (net (code "55") (name "P4_1") (class "Default")
      (node (ref "SV5") (pin "4") (pinfunction "4_4") (pintype "passive"))
      (node (ref "U$2") (pin "P$20") (pinfunction "P$20_P$20") (pintype "bidirectional"))
    )
    (net (code "56") (name "P4_2") (class "Default")
      (node (ref "SV5") (pin "13") (pinfunction "13_13") (pintype "passive"))
      (node (ref "U$2") (pin "P$29") (pinfunction "P$29_P$29") (pintype "bidirectional"))
    )
    (net (code "57") (name "P4_3") (class "Default")
      (node (ref "SV5") (pin "14") (pinfunction "14_14") (pintype "passive"))
      (node (ref "U$2") (pin "P$30") (pinfunction "P$30_P$30") (pintype "bidirectional"))
    )
    (net (code "58") (name "P4_4") (class "Default")
      (node (ref "LED4") (pin "1") (pinfunction "A_1") (pintype "bidirectional"))
      (node (ref "SV4") (pin "3") (pinfunction "3_3") (pintype "passive"))
      (node (ref "U$2") (pin "P$31") (pinfunction "P$31_P$31") (pintype "bidirectional"))
    )
    (net (code "59") (name "P4_5") (class "Default")
      (node (ref "LED3") (pin "1") (pinfunction "A_1") (pintype "bidirectional"))
      (node (ref "SV4") (pin "4") (pinfunction "4_4") (pintype "passive"))
      (node (ref "U$2") (pin "P$32") (pinfunction "P$32_P$32") (pintype "bidirectional"))
    )
    (net (code "60") (name "P4_6") (class "Default")
      (node (ref "LED2") (pin "1") (pinfunction "A_1") (pintype "bidirectional"))
      (node (ref "SV4") (pin "5") (pinfunction "5_5") (pintype "passive"))
      (node (ref "U$2") (pin "P$33") (pinfunction "P$33_P$33") (pintype "bidirectional"))
    )
    (net (code "61") (name "P4_7") (class "Default")
      (node (ref "LED1") (pin "1") (pinfunction "A_1") (pintype "bidirectional"))
      (node (ref "SV4") (pin "6") (pinfunction "6_6") (pintype "passive"))
      (node (ref "U$2") (pin "P$34") (pinfunction "P$34_P$34") (pintype "bidirectional"))
    )
    (net (code "62") (name "P5_0") (class "Default")
      (node (ref "SV1") (pin "7") (pinfunction "7_7") (pintype "passive"))
      (node (ref "U$2") (pin "P$64") (pinfunction "P$64_P$64") (pintype "bidirectional"))
    )
    (net (code "63") (name "P5_2") (class "Default")
      (node (ref "SV1") (pin "10") (pinfunction "10_10") (pintype "passive"))
      (node (ref "U$2") (pin "P$62") (pinfunction "P$62_P$62") (pintype "bidirectional"))
    )
    (net (code "64") (name "P5_4") (class "Default")
      (node (ref "SV3") (pin "4") (pinfunction "4_4") (pintype "passive"))
      (node (ref "U$2") (pin "P$50") (pinfunction "P$50_P$50") (pintype "bidirectional"))
    )
    (net (code "65") (name "P5_5") (class "Default")
      (node (ref "SV3") (pin "6") (pinfunction "6_6") (pintype "passive"))
      (node (ref "U$2") (pin "P$49") (pinfunction "P$49_P$49") (pintype "bidirectional"))
    )
    (net (code "66") (name "P5_6") (class "Default")
      (node (ref "SV3") (pin "3") (pinfunction "3_3") (pintype "passive"))
      (node (ref "U$2") (pin "P$48") (pinfunction "P$48_P$48") (pintype "bidirectional"))
    )
    (net (code "67") (name "P5_7") (class "Default")
      (node (ref "SV3") (pin "5") (pinfunction "5_5") (pintype "passive"))
      (node (ref "U$2") (pin "P$47") (pinfunction "P$47_P$47") (pintype "bidirectional"))
    )
    (net (code "68") (name "P6_1") (class "Default")
      (node (ref "R6") (pin "1") (pinfunction "P$1_1") (pintype "passive"))
      (node (ref "U$2") (pin "P$36") (pinfunction "P$36_P$36") (pintype "bidirectional"))
      (node (ref "U$78") (pin "P$1") (pinfunction "P$1_P$1") (pintype "bidirectional"))
      (node (ref "X9") (pin "3") (pinfunction "1_3") (pintype "passive"))
    )
    (net (code "69") (name "P6_3") (class "Default")
      (node (ref "R7") (pin "1") (pinfunction "P$1_1") (pintype "passive"))
      (node (ref "U$2") (pin "P$38") (pinfunction "P$38_P$38") (pintype "bidirectional"))
      (node (ref "U$79") (pin "P$1") (pinfunction "P$1_P$1") (pintype "bidirectional"))
      (node (ref "X9") (pin "4") (pinfunction "1_4") (pintype "passive"))
    )
    (net (code "70") (name "P6_4") (class "Default")
      (node (ref "SV1") (pin "6") (pinfunction "6_6") (pintype "passive"))
      (node (ref "SV2") (pin "6") (pinfunction "6_6") (pintype "passive"))
      (node (ref "U$2") (pin "P$70") (pinfunction "P$70_P$70") (pintype "bidirectional"))
    )
    (net (code "71") (name "P6_6") (class "Default")
      (node (ref "SV1") (pin "5") (pinfunction "5_5") (pintype "passive"))
      (node (ref "SV2") (pin "5") (pinfunction "5_5") (pintype "passive"))
      (node (ref "U$2") (pin "P$68") (pinfunction "P$68_P$68") (pintype "bidirectional"))
    )
    (net (code "72") (name "P12_0") (class "Default")
      (node (ref "CN1") (pin "3") (pinfunction "3_3") (pintype "bidirectional"))
      (node (ref "U$2") (pin "P$15") (pinfunction "P$15_P$15") (pintype "bidirectional"))
    )
    (net (code "73") (name "P12_1") (class "Default")
      (node (ref "J1") (pin "3") (pinfunction "R_3") (pintype "input"))
      (node (ref "R12") (pin "1") (pinfunction "P$1_1") (pintype "passive"))
      (node (ref "U$2") (pin "P$16") (pinfunction "P$16_P$16") (pintype "bidirectional"))
    )
    (net (code "74") (name "P12_2") (class "Default")
      (node (ref "CN1") (pin "4") (pinfunction "4_4") (pintype "bidirectional"))
      (node (ref "U$2") (pin "P$17") (pinfunction "P$17_P$17") (pintype "bidirectional"))
    )
    (net (code "75") (name "P12_3") (class "Default")
      (node (ref "U$2") (pin "P$18") (pinfunction "P$18_P$18") (pintype "bidirectional"))
      (node (ref "U$41") (pin "P$2") (pinfunction "PLUS_P$2") (pintype "bidirectional"))
    )
    (net (code "76") (name "P12_4") (class "Default")
      (node (ref "SV1") (pin "3") (pinfunction "3_3") (pintype "passive"))
      (node (ref "SV2") (pin "3") (pinfunction "3_3") (pintype "passive"))
      (node (ref "U$2") (pin "P$72") (pinfunction "P$72_P$72") (pintype "bidirectional"))
    )
    (net (code "77") (name "P12_5") (class "Default")
      (node (ref "M1") (pin "10") (pinfunction "STO_10") (pintype "passive"))
      (node (ref "U$2") (pin "P$71") (pinfunction "P$71_P$71") (pintype "bidirectional"))
    )
    (net (code "78") (name "P12_6") (class "Default")
      (node (ref "R5") (pin "1") (pinfunction "P$1_1") (pintype "passive"))
      (node (ref "U$2") (pin "P$52") (pinfunction "P$52_P$52") (pintype "bidirectional"))
      (node (ref "U$77") (pin "P$1") (pinfunction "P$1_P$1") (pintype "bidirectional"))
      (node (ref "X1") (pin "4") (pinfunction "1_4") (pintype "passive"))
      (node (ref "X2") (pin "4") (pinfunction "1_4") (pintype "passive"))
      (node (ref "X3") (pin "4") (pinfunction "1_4") (pintype "passive"))
    )
    (net (code "79") (name "P12_7") (class "Default")
      (node (ref "U$2") (pin "P$51") (pinfunction "P$51_P$51") (pintype "bidirectional"))
      (node (ref "U$43") (pin "2") (pinfunction "-CS_2") (pintype "bidirectional"))
      (node (ref "U$86") (pin "P$1") (pinfunction "P$1_P$1") (pintype "bidirectional"))
    )
    (net (code "80") (name "SWDCK") (class "Default")
      (node (ref "CN3") (pin "3") (pinfunction "3_3") (pintype "bidirectional"))
      (node (ref "U$2") (pin "P$59") (pinfunction "P$59_P$59") (pintype "bidirectional"))
    )
    (net (code "81") (name "SWDIO") (class "Default")
      (node (ref "CN3") (pin "4") (pinfunction "4_4") (pintype "bidirectional"))
      (node (ref "U$2") (pin "P$60") (pinfunction "P$60_P$60") (pintype "bidirectional"))
    )
    (net (code "82") (name "SWO") (class "Default")
      (node (ref "CN3") (pin "5") (pinfunction "5_5") (pintype "bidirectional"))
      (node (ref "U$2") (pin "P$57") (pinfunction "P$57_P$57") (pintype "bidirectional"))
    )
    (net (code "83") (name "V_BATT") (class "Default")
      (node (ref "C4") (pin "P$1") (pinfunction "1_P$1") (pintype "passive"))
      (node (ref "C5") (pin "P$1") (pinfunction "1_P$1") (pintype "passive"))
      (node (ref "PH2") (pin "2") (pinfunction "2_2") (pintype "passive"))
      (node (ref "U$2") (pin "P$66") (pinfunction "P$66_P$66") (pintype "bidirectional"))
      (node (ref "XH2") (pin "P$2") (pinfunction "1_P$2") (pintype "passive"))
      (node (ref "ZH2") (pin "2") (pinfunction "2_2") (pintype "bidirectional"))
    )
    (net (code "84") (name "V_DDA") (class "Default")
      (node (ref "U$2") (pin "P$6") (pinfunction "P$6_P$6") (pintype "bidirectional"))
    )
    (net (code "85") (name "V_DDA2") (class "Default")
      (node (ref "U$2") (pin "P$45") (pinfunction "P$45_P$45") (pintype "bidirectional"))
    )
    (net (code "86") (name "V_DDIN") (class "Default")
      (node (ref "C3") (pin "P$1") (pinfunction "1_P$1") (pintype "passive"))
      (node (ref "J1") (pin "1") (pinfunction "P_1") (pintype "power_in"))
      (node (ref "U$2") (pin "P$2") (pinfunction "P$2_P$2") (pintype "bidirectional"))
    )
    (net (code "87") (name "V_DDIN2") (class "Default")
      (node (ref "U$2") (pin "P$41") (pinfunction "P$41_P$41") (pintype "bidirectional"))
    )
    (net (code "88") (name "V_SSA") (class "Default")
      (node (ref "U$2") (pin "P$5") (pinfunction "P$5_P$5") (pintype "bidirectional"))
    )
    (net (code "89") (name "V_SSA2") (class "Default")
      (node (ref "U$2") (pin "P$46") (pinfunction "P$46_P$46") (pintype "bidirectional"))
    )
    (net (code "90") (name "XRES") (class "Default")
      (node (ref "CN3") (pin "6") (pinfunction "6_6") (pintype "bidirectional"))
      (node (ref "U$2") (pin "P$65") (pinfunction "P$65_P$65") (pintype "bidirectional"))
    )
    (net (code "91") (name "unconnected-(IC1-VREF-Pad5)") (class "Default")
      (node (ref "IC1") (pin "5") (pinfunction "VREF_5") (pintype "bidirectional"))
    )
    (net (code "92") (name "unconnected-(M1-MCLR-Pad1)") (class "Default")
      (node (ref "M1") (pin "1") (pinfunction "MCLR_1") (pintype "passive"))
    )
    (net (code "93") (name "unconnected-(M1-PGEC-Pad5)") (class "Default")
      (node (ref "M1") (pin "5") (pinfunction "PGEC_5") (pintype "passive"))
    )
    (net (code "94") (name "unconnected-(M1-PGED-Pad4)") (class "Default")
      (node (ref "M1") (pin "4") (pinfunction "PGED_4") (pintype "passive"))
    )
    (net (code "95") (name "unconnected-(U$43-NC-Pad1)") (class "Default")
      (node (ref "U$43") (pin "1") (pinfunction "NC_1") (pintype "bidirectional"))
    )
    (net (code "96") (name "unconnected-(U$43-RSV-Pad8)") (class "Default")
      (node (ref "U$43") (pin "8") (pinfunction "RSV_8") (pintype "bidirectional"))
    )
  )
)
